# DI.net
KiCad netlist of a schematic drawn in Altium Designer
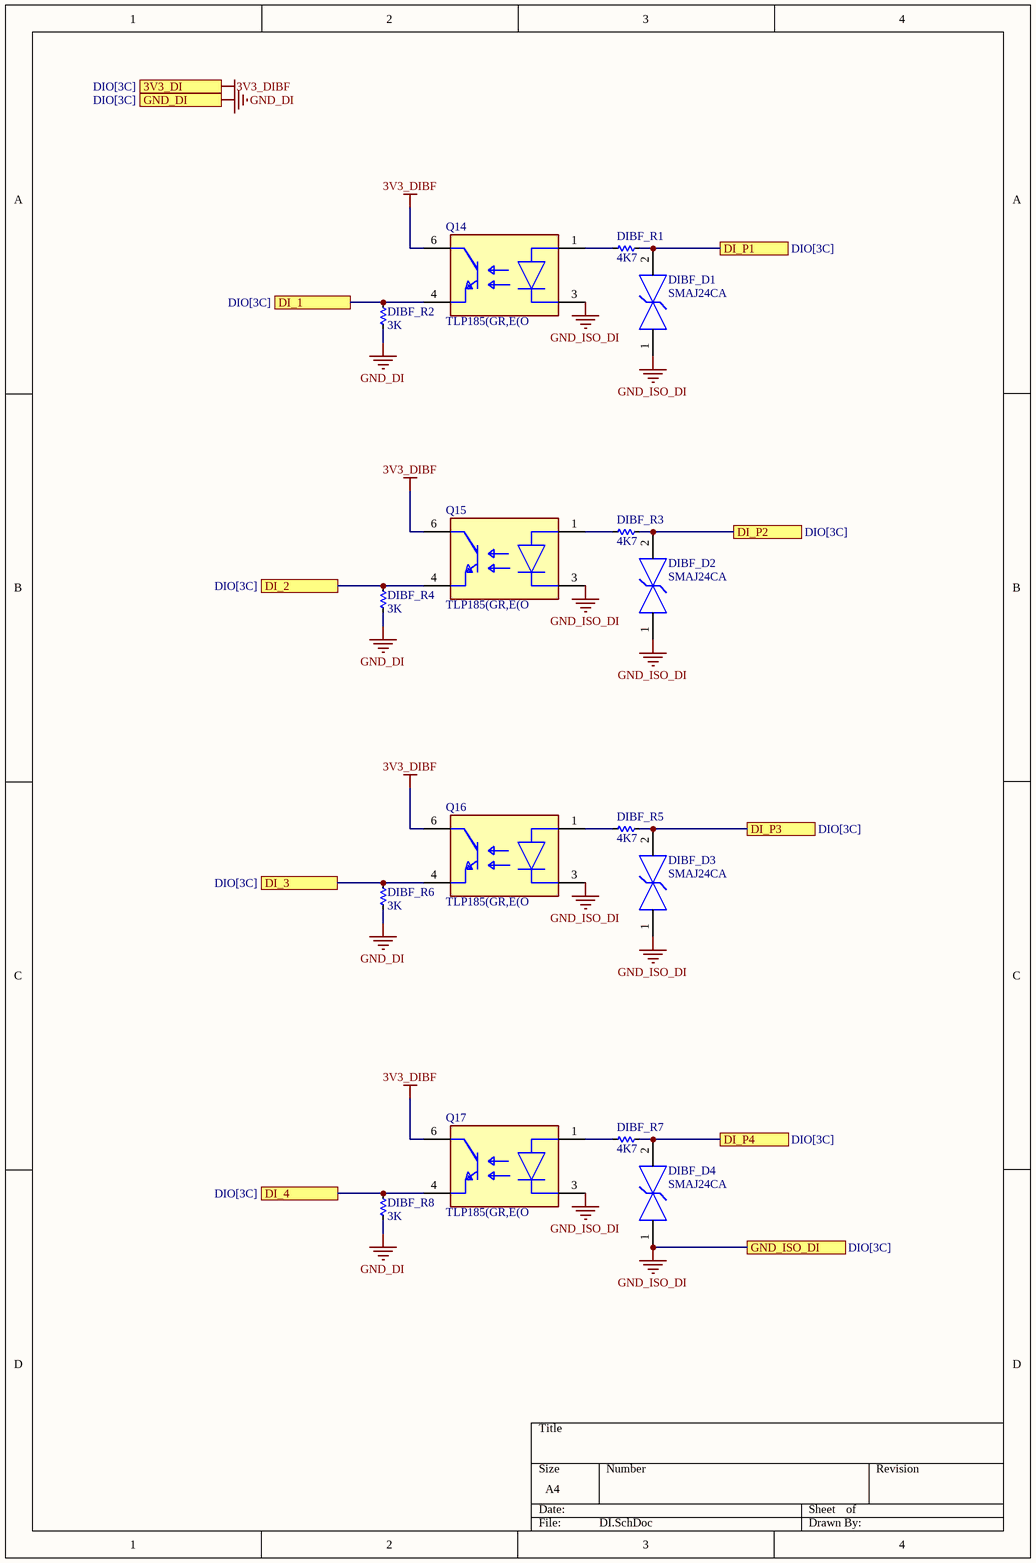
[diagram p0: DI.SchDoc]

(export (version "E")
  (design (tool "Eeschema 10.0.6"))
  (components
    (comp (ref "DIBF_D1")
      (value "SMAJ24CA")
      (footprint "FP-SMAJ-CA-MFG")
      (description "TVS DIODE 24V 38.9V DO214AC")
      (fields
        (field (name "MANUFACTURER") "Littelfuse")
        (field (name "OCTOPART") "https://octopart.com/smaj24ca-littelfuse-350011")
      )
      (libsource (lib "Altium Content Vault") (part "876f4347bf90aa6f500f43e3cd03972"))
    )
    (comp (ref "DIBF_D2")
      (value "SMAJ24CA")
      (footprint "FP-SMAJ-CA-MFG")
      (description "TVS DIODE 24V 38.9V DO214AC")
      (fields
        (field (name "MANUFACTURER") "Littelfuse")
        (field (name "OCTOPART") "https://octopart.com/smaj24ca-littelfuse-350011")
      )
      (libsource (lib "Altium Content Vault") (part "876f4347bf90aa6f500f43e3cd03972"))
    )
    (comp (ref "DIBF_D3")
      (value "SMAJ24CA")
      (footprint "FP-SMAJ-CA-MFG")
      (description "TVS DIODE 24V 38.9V DO214AC")
      (fields
        (field (name "MANUFACTURER") "Littelfuse")
        (field (name "OCTOPART") "https://octopart.com/smaj24ca-littelfuse-350011")
      )
      (libsource (lib "Altium Content Vault") (part "876f4347bf90aa6f500f43e3cd03972"))
    )
    (comp (ref "DIBF_D4")
      (value "SMAJ24CA")
      (footprint "FP-SMAJ-CA-MFG")
      (description "TVS DIODE 24V 38.9V DO214AC")
      (fields
        (field (name "MANUFACTURER") "Littelfuse")
        (field (name "OCTOPART") "https://octopart.com/smaj24ca-littelfuse-350011")
      )
      (libsource (lib "Altium Content Vault") (part "876f4347bf90aa6f500f43e3cd03972"))
    )
    (comp (ref "DIBF_R1")
      (value "4K7")
      (footprint "RES-SMD-0805")
      (description "Res 0805 1%")
      (fields
        (field (name "MANUFACTURER") "Generic Components")
        (field (name "PUBLISHER") "Altium Hobart Technology Centre")
      )
      (libsource (lib "TechMT.VN_Lib_Project v2") (part "Res-SMD"))
    )
    (comp (ref "DIBF_R2")
      (value "3K")
      (footprint "RES-SMD-0805")
      (description "Res 0805 1%")
      (fields
        (field (name "MANUFACTURER") "Generic Components")
        (field (name "PUBLISHER") "Altium Hobart Technology Centre")
      )
      (libsource (lib "TechMT.VN_Lib_Project v2") (part "Res-SMD"))
    )
    (comp (ref "DIBF_R3")
      (value "4K7")
      (footprint "RES-SMD-0805")
      (description "Res 0805 1%")
      (fields
        (field (name "MANUFACTURER") "Generic Components")
        (field (name "PUBLISHER") "Altium Hobart Technology Centre")
      )
      (libsource (lib "TechMT.VN_Lib_Project v2") (part "Res-SMD"))
    )
    (comp (ref "DIBF_R4")
      (value "3K")
      (footprint "RES-SMD-0805")
      (description "Res 0805 1%")
      (fields
        (field (name "MANUFACTURER") "Generic Components")
        (field (name "PUBLISHER") "Altium Hobart Technology Centre")
      )
      (libsource (lib "TechMT.VN_Lib_Project v2") (part "Res-SMD"))
    )
    (comp (ref "DIBF_R5")
      (value "4K7")
      (footprint "RES-SMD-0805")
      (description "Res 0805 1%")
      (fields
        (field (name "MANUFACTURER") "Generic Components")
        (field (name "PUBLISHER") "Altium Hobart Technology Centre")
      )
      (libsource (lib "TechMT.VN_Lib_Project v2") (part "Res-SMD"))
    )
    (comp (ref "DIBF_R6")
      (value "3K")
      (footprint "RES-SMD-0805")
      (description "Res 0805 1%")
      (fields
        (field (name "MANUFACTURER") "Generic Components")
        (field (name "PUBLISHER") "Altium Hobart Technology Centre")
      )
      (libsource (lib "TechMT.VN_Lib_Project v2") (part "Res-SMD"))
    )
    (comp (ref "DIBF_R7")
      (value "4K7")
      (footprint "RES-SMD-0805")
      (description "Res 0805 1%")
      (fields
        (field (name "MANUFACTURER") "Generic Components")
        (field (name "PUBLISHER") "Altium Hobart Technology Centre")
      )
      (libsource (lib "TechMT.VN_Lib_Project v2") (part "Res-SMD"))
    )
    (comp (ref "DIBF_R8")
      (value "3K")
      (footprint "RES-SMD-0805")
      (description "Res 0805 1%")
      (fields
        (field (name "MANUFACTURER") "Generic Components")
        (field (name "PUBLISHER") "Altium Hobart Technology Centre")
      )
      (libsource (lib "TechMT.VN_Lib_Project v2") (part "Res-SMD"))
    )
    (comp (ref "Q14")
      (value "TLP185(GR,E(O")
      (footprint "FP-11-4M1S-MFG")
      (description "OPTOISO 3.75KV TRANS 6-SO 4 LEAD")
      (fields
        (field (name "OCTOPART") "https://octopart.com/tlp185%28gr%2Ce%28o-toshiba-23809180")
        (field (name "MANUFACTURER") "Toshiba")
      )
      (libsource (lib "Altium Content Vault") (part "aca734292714cba98c36f1bc381f871"))
    )
    (comp (ref "Q15")
      (value "TLP185(GR,E(O")
      (footprint "FP-11-4M1S-MFG")
      (description "OPTOISO 3.75KV TRANS 6-SO 4 LEAD")
      (fields
        (field (name "OCTOPART") "https://octopart.com/tlp185%28gr%2Ce%28o-toshiba-23809180")
        (field (name "MANUFACTURER") "Toshiba")
      )
      (libsource (lib "Altium Content Vault") (part "aca734292714cba98c36f1bc381f871"))
    )
    (comp (ref "Q16")
      (value "TLP185(GR,E(O")
      (footprint "FP-11-4M1S-MFG")
      (description "OPTOISO 3.75KV TRANS 6-SO 4 LEAD")
      (fields
        (field (name "OCTOPART") "https://octopart.com/tlp185%28gr%2Ce%28o-toshiba-23809180")
        (field (name "MANUFACTURER") "Toshiba")
      )
      (libsource (lib "Altium Content Vault") (part "aca734292714cba98c36f1bc381f871"))
    )
    (comp (ref "Q17")
      (value "TLP185(GR,E(O")
      (footprint "FP-11-4M1S-MFG")
      (description "OPTOISO 3.75KV TRANS 6-SO 4 LEAD")
      (fields
        (field (name "OCTOPART") "https://octopart.com/tlp185%28gr%2Ce%28o-toshiba-23809180")
        (field (name "MANUFACTURER") "Toshiba")
      )
      (libsource (lib "Altium Content Vault") (part "aca734292714cba98c36f1bc381f871"))
    )
  )
  (nets
    (net (code "1") (name "/DI_1") (class "Default")
      (node (ref "DIBF_R2") (pin "1") (pinfunction "1_1") (pintype "passive"))
      (node (ref "Q14") (pin "4") (pinfunction "E_4") (pintype "passive"))
    )
    (net (code "2") (name "/DI_2") (class "Default")
      (node (ref "DIBF_R4") (pin "1") (pinfunction "1_1") (pintype "passive"))
      (node (ref "Q15") (pin "4") (pinfunction "E_4") (pintype "passive"))
    )
    (net (code "3") (name "/DI_3") (class "Default")
      (node (ref "DIBF_R6") (pin "1") (pinfunction "1_1") (pintype "passive"))
      (node (ref "Q16") (pin "4") (pinfunction "E_4") (pintype "passive"))
    )
    (net (code "4") (name "/DI_4") (class "Default")
      (node (ref "DIBF_R8") (pin "1") (pinfunction "1_1") (pintype "passive"))
      (node (ref "Q17") (pin "4") (pinfunction "E_4") (pintype "passive"))
    )
    (net (code "5") (name "/DI_P1") (class "Default")
      (node (ref "DIBF_D1") (pin "2") (pinfunction "2_2") (pintype "passive"))
      (node (ref "DIBF_R1") (pin "1") (pinfunction "1_1") (pintype "passive"))
    )
    (net (code "6") (name "/DI_P2") (class "Default")
      (node (ref "DIBF_D2") (pin "2") (pinfunction "2_2") (pintype "passive"))
      (node (ref "DIBF_R3") (pin "1") (pinfunction "1_1") (pintype "passive"))
    )
    (net (code "7") (name "/DI_P3") (class "Default")
      (node (ref "DIBF_D3") (pin "2") (pinfunction "2_2") (pintype "passive"))
      (node (ref "DIBF_R5") (pin "1") (pinfunction "1_1") (pintype "passive"))
    )
    (net (code "8") (name "/DI_P4") (class "Default")
      (node (ref "DIBF_D4") (pin "2") (pinfunction "2_2") (pintype "passive"))
      (node (ref "DIBF_R7") (pin "1") (pinfunction "1_1") (pintype "passive"))
    )
    (net (code "9") (name "3V3_DIBF") (class "Default")
      (node (ref "Q14") (pin "6") (pinfunction "C_6") (pintype "passive"))
      (node (ref "Q15") (pin "6") (pinfunction "C_6") (pintype "passive"))
      (node (ref "Q16") (pin "6") (pinfunction "C_6") (pintype "passive"))
      (node (ref "Q17") (pin "6") (pinfunction "C_6") (pintype "passive"))
    )
    (net (code "10") (name "GND_DI") (class "Default")
      (node (ref "DIBF_R2") (pin "2") (pinfunction "2_2") (pintype "passive"))
      (node (ref "DIBF_R4") (pin "2") (pinfunction "2_2") (pintype "passive"))
      (node (ref "DIBF_R6") (pin "2") (pinfunction "2_2") (pintype "passive"))
      (node (ref "DIBF_R8") (pin "2") (pinfunction "2_2") (pintype "passive"))
    )
    (net (code "11") (name "GND_ISO_DI") (class "Default")
      (node (ref "DIBF_D1") (pin "1") (pinfunction "1_1") (pintype "passive"))
      (node (ref "DIBF_D2") (pin "1") (pinfunction "1_1") (pintype "passive"))
      (node (ref "DIBF_D3") (pin "1") (pinfunction "1_1") (pintype "passive"))
      (node (ref "DIBF_D4") (pin "1") (pinfunction "1_1") (pintype "passive"))
      (node (ref "Q14") (pin "3") (pinfunction "C_3") (pintype "passive"))
      (node (ref "Q15") (pin "3") (pinfunction "C_3") (pintype "passive"))
      (node (ref "Q16") (pin "3") (pinfunction "C_3") (pintype "passive"))
      (node (ref "Q17") (pin "3") (pinfunction "C_3") (pintype "passive"))
    )
    (net (code "12") (name "Net-(Q14-A)") (class "Default")
      (node (ref "DIBF_R1") (pin "2") (pinfunction "2_2") (pintype "passive"))
      (node (ref "Q14") (pin "1") (pinfunction "A_1") (pintype "passive"))
    )
    (net (code "13") (name "Net-(Q15-A)") (class "Default")
      (node (ref "DIBF_R3") (pin "2") (pinfunction "2_2") (pintype "passive"))
      (node (ref "Q15") (pin "1") (pinfunction "A_1") (pintype "passive"))
    )
    (net (code "14") (name "Net-(Q16-A)") (class "Default")
      (node (ref "DIBF_R5") (pin "2") (pinfunction "2_2") (pintype "passive"))
      (node (ref "Q16") (pin "1") (pinfunction "A_1") (pintype "passive"))
    )
    (net (code "15") (name "Net-(Q17-A)") (class "Default")
      (node (ref "DIBF_R7") (pin "2") (pinfunction "2_2") (pintype "passive"))
      (node (ref "Q17") (pin "1") (pinfunction "A_1") (pintype "passive"))
    )
  )
)
